# MACH.net
KiCad netlist of a schematic drawn in Altium Designer
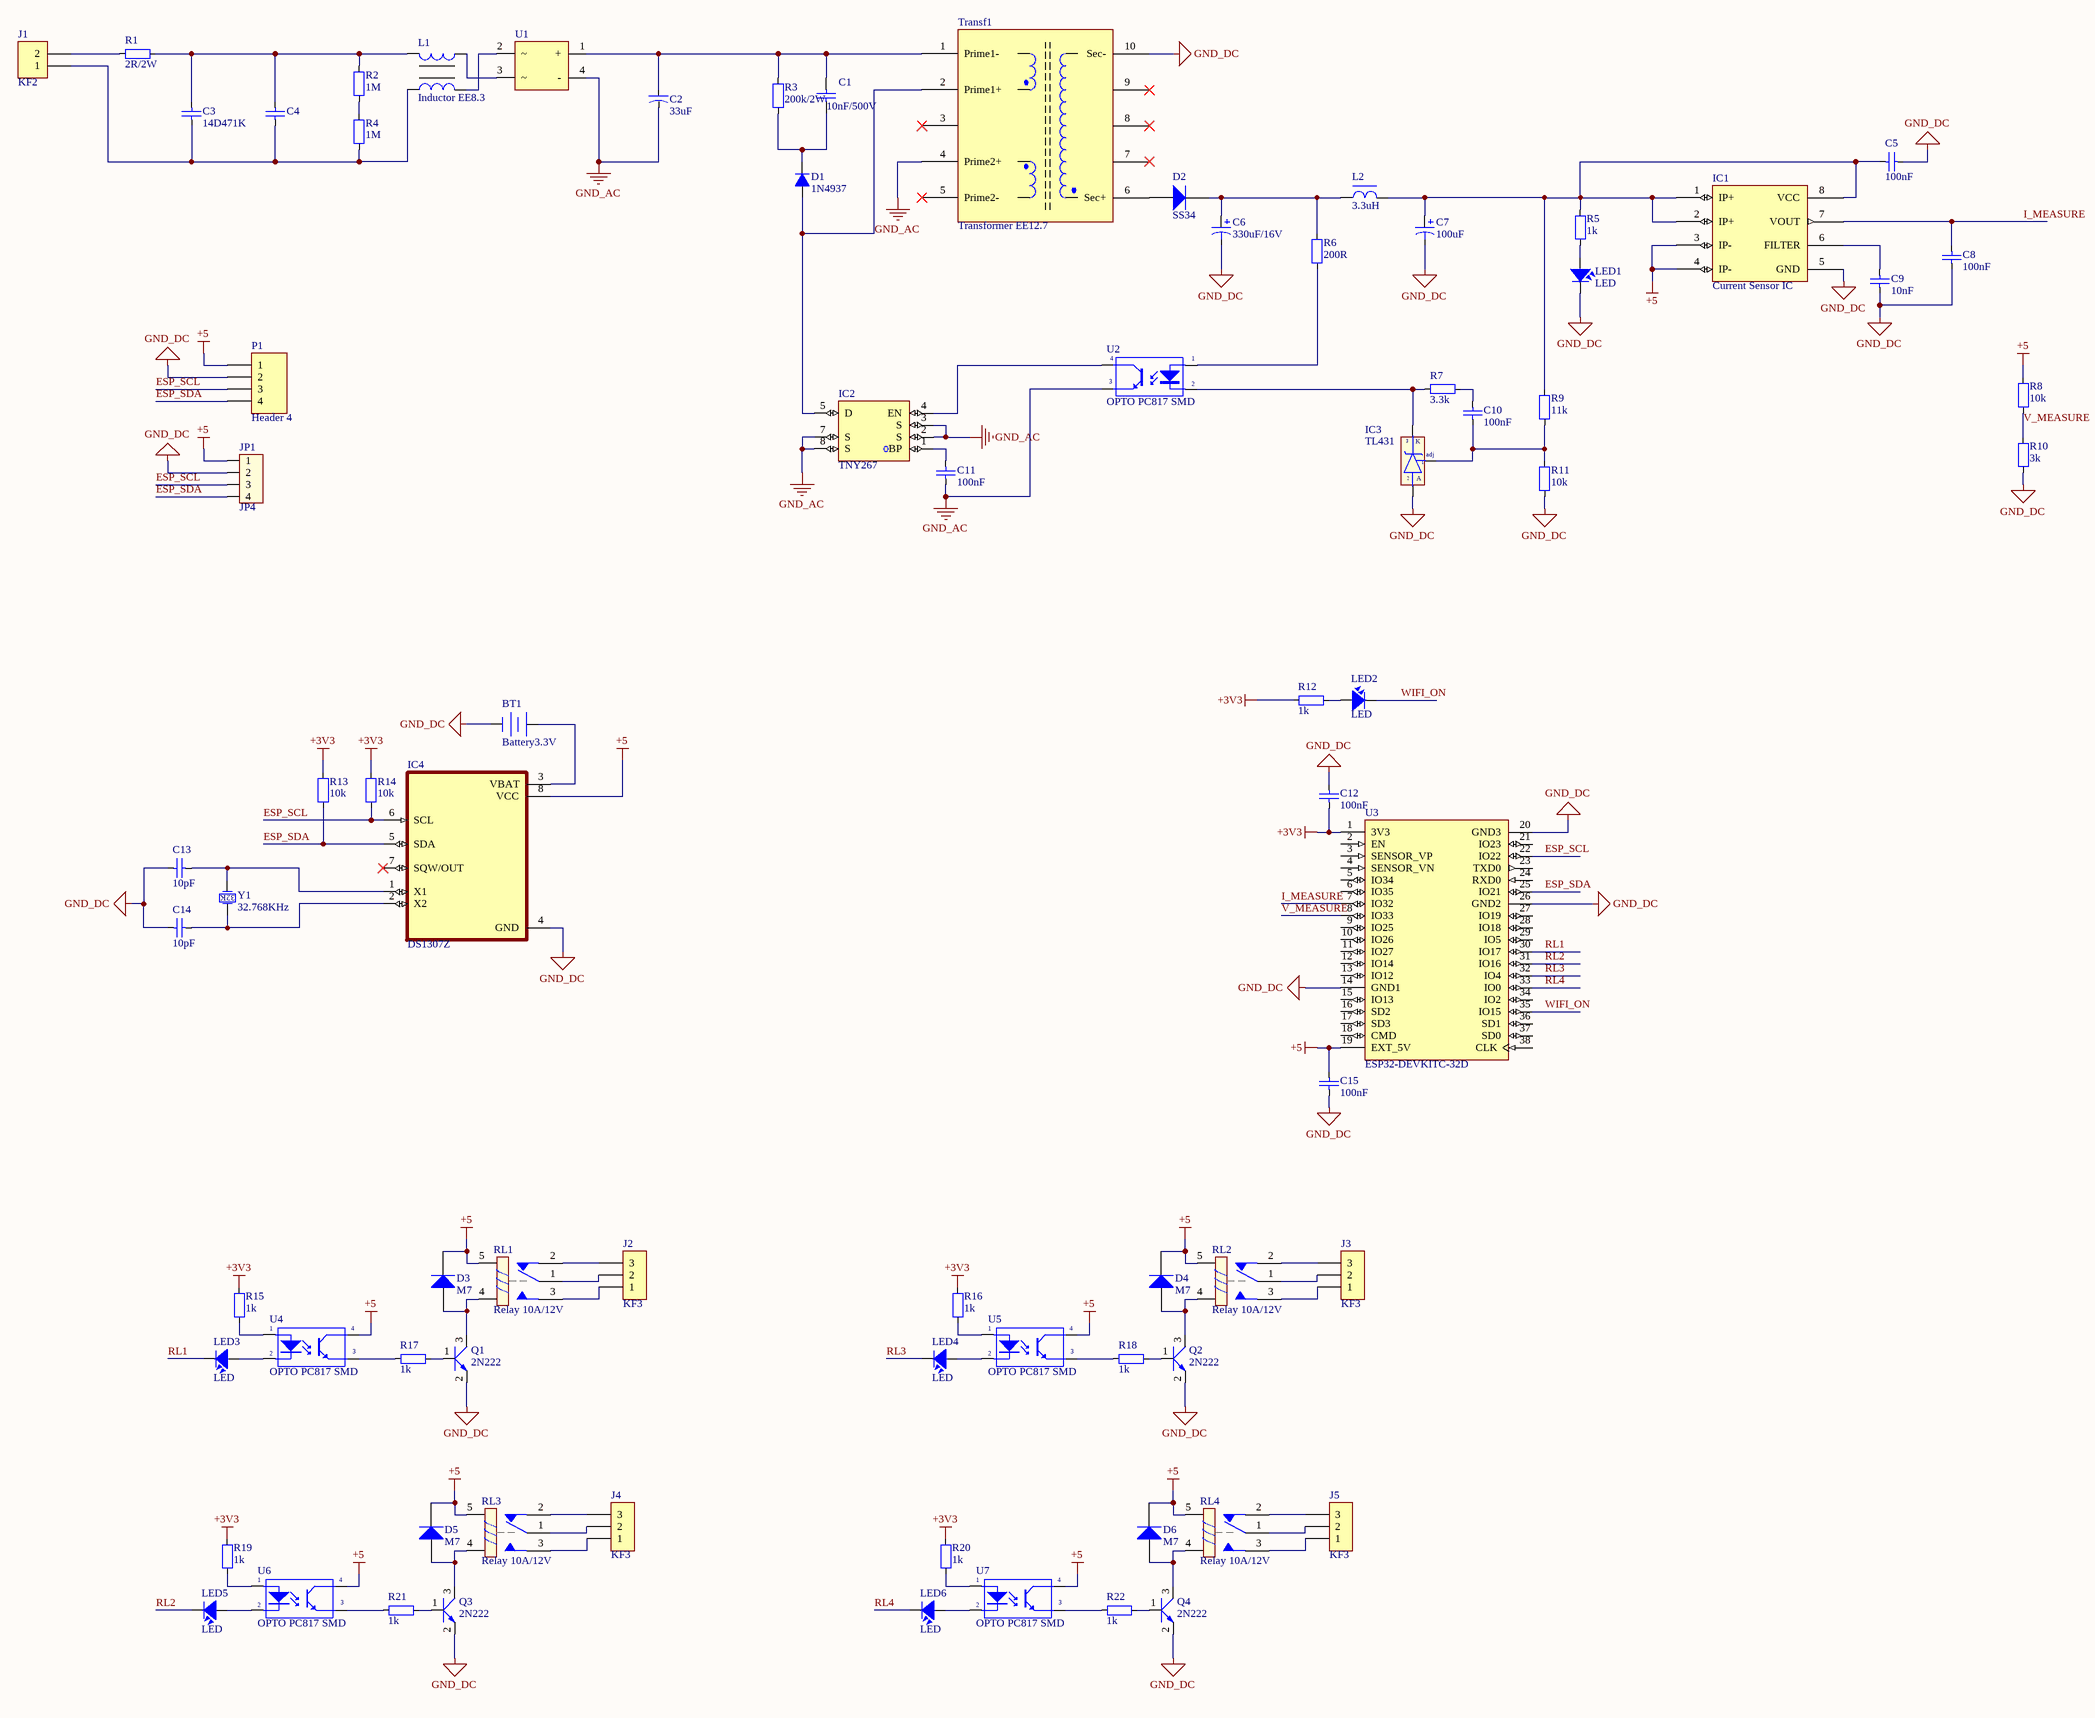
[diagram p0: MACH.SchDoc]

(export (version "E")
  (design (tool "Eeschema 10.0.6"))
  (components
    (comp (ref "BT1")
      (value "Battery3.3V")
      (footprint "CR1220 SMD")
      (description "Multicell Battery")
      (fields (field (name "PUBLISHER") "Altium Limited"))
      (libsource (lib "My Library") (part "Battery3.3V"))
    )
    (comp (ref "C1")
      (value "10nF/500V")
      (footprint "tu gom")
      (description "Tụ gốm 103 10nF 500V")
      (libsource (lib "Altium_Lib_by_KhueNguyenCreator") (part "Tu gom 103 50V"))
    )
    (comp (ref "C2")
      (value "33uF")
      (footprint "CA-ALU-8")
      (description "Capacitor (Semiconductor SIM Model)")
      (fields (field (name "PUBLISHER") "Altium Limited"))
      (libsource (lib "My Library") (part "CAP-ALU-DIP"))
    )
    (comp (ref "C3")
      (value "14D471K")
      (footprint "103/2KV")
      (description "Capacitor Ceramic 2KV")
      (fields (field (name "PUBLISHER") "Altium Limited"))
      (libsource (lib "My Library") (part "Cap2KV"))
    )
    (comp (ref "C4")
      (value "Cap AC filter")
      (footprint "Cap AC filter")
      (description "Tụ lọc nguồn AC 0.1uf 275v 10mm")
      (libsource (lib "My Library") (part "Cap AC filter"))
    )
    (comp (ref "C5")
      (value "100nF")
      (footprint "CAP_0805")
      (description "Capacitor")
      (fields (field (name "PUBLISHER") "Altium Limited"))
      (libsource (lib "My Library") (part "CapSMD"))
    )
    (comp (ref "C6")
      (value "330uF/16V")
      (footprint "C8mm")
      (description "Polarized Capacitor (Axial)")
      (fields (field (name "PUBLISHER") "Altium Limited"))
      (libsource (lib "My Library") (part "Cap Pol"))
    )
    (comp (ref "C7")
      (value "100uF")
      (footprint "C8mm")
      (description "Polarized Capacitor (Axial)")
      (fields (field (name "PUBLISHER") "Altium Limited"))
      (libsource (lib "My Library") (part "Cap Pol"))
    )
    (comp (ref "C8")
      (value "100nF")
      (footprint "CAP_0805")
      (description "Capacitor")
      (fields (field (name "PUBLISHER") "Altium Limited"))
      (libsource (lib "My Library") (part "CapSMD"))
    )
    (comp (ref "C9")
      (value "10nF")
      (footprint "CAP_0805")
      (description "Capacitor")
      (fields (field (name "PUBLISHER") "Altium Limited"))
      (libsource (lib "My Library") (part "CapSMD"))
    )
    (comp (ref "C10")
      (value "100nF")
      (footprint "CAP_0805")
      (description "Capacitor")
      (fields (field (name "PUBLISHER") "Altium Limited"))
      (libsource (lib "My Library") (part "CapSMD"))
    )
    (comp (ref "C11")
      (value "100nF")
      (footprint "CAP_0805")
      (description "Capacitor")
      (fields (field (name "PUBLISHER") "Altium Limited"))
      (libsource (lib "My Library") (part "CapSMD"))
    )
    (comp (ref "C12")
      (value "100nF")
      (footprint "CAP_0805")
      (description "Capacitor")
      (fields (field (name "PUBLISHER") "Altium Limited"))
      (libsource (lib "My Library") (part "CapSMD"))
    )
    (comp (ref "C13")
      (value "10pF")
      (footprint "CAP_0603")
      (description "Capacitor")
      (fields (field (name "PUBLISHER") "Altium Limited"))
      (libsource (lib "My Library") (part "CapSMD"))
    )
    (comp (ref "C14")
      (value "10pF")
      (footprint "CAP_0603")
      (description "Capacitor")
      (fields (field (name "PUBLISHER") "Altium Limited"))
      (libsource (lib "My Library") (part "CapSMD"))
    )
    (comp (ref "C15")
      (value "100nF")
      (footprint "CAP_0805")
      (description "Capacitor")
      (fields (field (name "PUBLISHER") "Altium Limited"))
      (libsource (lib "My Library") (part "CapSMD"))
    )
    (comp (ref "D1")
      (value "1N4937")
      (footprint "D5AN")
      (description "Diode 5A")
      (libsource (lib "My Library") (part "D5A"))
    )
    (comp (ref "D2")
      (value "SS34")
      (footprint "DIODE SMA")
      (description "Dán")
      (libsource (lib "Altium_Lib_by_KhueNguyenCreator") (part "Diode SS34 ( 1N5822 )"))
    )
    (comp (ref "D3")
      (value "M7")
      (footprint "DIODE SMA")
      (description "Dán")
      (libsource (lib "Altium_Lib_by_KhueNguyenCreator") (part "Diode M7 ( 4007 )"))
    )
    (comp (ref "D4")
      (value "M7")
      (footprint "DIODE SMA")
      (description "Dán")
      (libsource (lib "Altium_Lib_by_KhueNguyenCreator") (part "Diode M7 ( 4007 )"))
    )
    (comp (ref "D5")
      (value "M7")
      (footprint "DIODE SMA")
      (description "Dán")
      (libsource (lib "Altium_Lib_by_KhueNguyenCreator") (part "Diode M7 ( 4007 )"))
    )
    (comp (ref "D6")
      (value "M7")
      (footprint "DIODE SMA")
      (description "Dán")
      (libsource (lib "Altium_Lib_by_KhueNguyenCreator") (part "Diode M7 ( 4007 )"))
    )
    (comp (ref "IC1")
      (value "Current Sensor IC")
      (footprint "SOIC-8")
      (libsource (lib "My Library") (part "ACS712"))
    )
    (comp (ref "IC2")
      (value "TNY267")
      (footprint "TNY264")
      (description "IC Power")
      (libsource (lib "My Library") (part "TNY264"))
    )
    (comp (ref "IC3")
      (value "TL431")
      (footprint "qto-92")
      (description "Programmable Shunt Regulator")
      (libsource (lib "My Library") (part "TL431"))
    )
    (comp (ref "IC4")
      (value "DS1307Z")
      (footprint "SOIC-8")
      (description "0x68")
      (libsource (lib "My Library") (part "DS1307Z"))
    )
    (comp (ref "J1")
      (value "KF2")
      (footprint "KF2-5.08")
      (fields
        (field (name "MANUFACTURER") "Würth Elektronik eiSos GmbH")
        (field (name "PARTNO") "691103110002")
        (field (name "CREATED BY") "Karrer Zheng")
      )
      (libsource (lib "My Library") (part "KF2"))
    )
    (comp (ref "J2")
      (value "KF3")
      (footprint "KF3-5.08")
      (fields
        (field (name "MANUFACTURER") "Würth Elektronik eiSos GmbH")
        (field (name "PARTNO") "691103110003")
        (field (name "CREATED BY") "Karrer Zheng")
      )
      (libsource (lib "My Library") (part "KF3"))
    )
    (comp (ref "J3")
      (value "KF3")
      (footprint "KF3-5.08")
      (fields
        (field (name "MANUFACTURER") "Würth Elektronik eiSos GmbH")
        (field (name "PARTNO") "691103110003")
        (field (name "CREATED BY") "Karrer Zheng")
      )
      (libsource (lib "My Library") (part "KF3"))
    )
    (comp (ref "J4")
      (value "KF3")
      (footprint "KF3-5.08")
      (fields
        (field (name "MANUFACTURER") "Würth Elektronik eiSos GmbH")
        (field (name "PARTNO") "691103110003")
        (field (name "CREATED BY") "Karrer Zheng")
      )
      (libsource (lib "My Library") (part "KF3"))
    )
    (comp (ref "J5")
      (value "KF3")
      (footprint "KF3-5.08")
      (fields
        (field (name "MANUFACTURER") "Würth Elektronik eiSos GmbH")
        (field (name "PARTNO") "691103110003")
        (field (name "CREATED BY") "Karrer Zheng")
      )
      (libsource (lib "My Library") (part "KF3"))
    )
    (comp (ref "JP1")
      (value "JP4")
      (footprint "CON4")
      (description "Connector 4")
      (libsource (lib "My Library") (part "Con4"))
    )
    (comp (ref "L1")
      (value "Inductor EE8.3")
      (footprint "Inductor EE8.3")
      (libsource (lib "My Library") (part "Inductor EE8.3"))
    )
    (comp (ref "L2")
      (value "3.3uH")
      (footprint "L-SMD-M-7.3x4.5")
      (description "Inductor")
      (libsource (lib "My Library") (part "L-DIP-1"))
    )
    (comp (ref "LED1")
      (value "LED")
      (footprint "LED-0805-Red")
      (description "LED Single colour Green and Red")
      (libsource (lib "My Library") (part "LED"))
    )
    (comp (ref "LED2")
      (value "LED")
      (footprint "LED-0805-Red")
      (description "LED Single colour Green and Red")
      (libsource (lib "My Library") (part "LED"))
    )
    (comp (ref "LED3")
      (value "LED")
      (footprint "LED-0805-Red")
      (description "LED Single colour Green and Red")
      (libsource (lib "My Library") (part "LED"))
    )
    (comp (ref "LED4")
      (value "LED")
      (footprint "LED-0805-Red")
      (description "LED Single colour Green and Red")
      (libsource (lib "My Library") (part "LED"))
    )
    (comp (ref "LED5")
      (value "LED")
      (footprint "LED-0805-Red")
      (description "LED Single colour Green and Red")
      (libsource (lib "My Library") (part "LED"))
    )
    (comp (ref "LED6")
      (value "LED")
      (footprint "LED-0805-Red")
      (description "LED Single colour Green and Red")
      (libsource (lib "My Library") (part "LED"))
    )
    (comp (ref "P1")
      (value "Header 4")
      (footprint "HDR1X4")
      (description "Header, 4-Pin")
      (fields (field (name "PUBLISHER") "Altium Limited"))
      (libsource (lib "Miscellaneous Connectors") (part "Header 4"))
    )
    (comp (ref "Q1")
      (value "2N222")
      (footprint "SOT23D")
      (description "NPN 600mW, ECB")
      (libsource (lib "My Library") (part "2N222"))
    )
    (comp (ref "Q2")
      (value "2N222")
      (footprint "SOT23D")
      (description "NPN 600mW, ECB")
      (libsource (lib "My Library") (part "2N222"))
    )
    (comp (ref "Q3")
      (value "2N222")
      (footprint "SOT23D")
      (description "NPN 600mW, ECB")
      (libsource (lib "My Library") (part "2N222"))
    )
    (comp (ref "Q4")
      (value "2N222")
      (footprint "SOT23D")
      (description "NPN 600mW, ECB")
      (libsource (lib "My Library") (part "2N222"))
    )
    (comp (ref "R1")
      (value "2R/2W")
      (footprint "RES-1WD")
      (description "Resistor - DIP")
      (libsource (lib "My Library") (part "Resistor - DIP"))
    )
    (comp (ref "R2")
      (value "1M")
      (footprint "RES-SMD-1206")
      (description "Resistor")
      (fields
        (field (name "MANUFACTURER") "Generic Components")
        (field (name "PUBLISHER") "Altium Hobart Technology Centre")
      )
      (libsource (lib "My Library") (part "Resistor - SMD"))
    )
    (comp (ref "R3")
      (value "200k/2W")
      (footprint "RES-1WD")
      (description "Resistor - DIP")
      (libsource (lib "My Library") (part "Resistor - DIP"))
    )
    (comp (ref "R4")
      (value "1M")
      (footprint "RES-SMD-1206")
      (description "Resistor")
      (fields
        (field (name "MANUFACTURER") "Generic Components")
        (field (name "PUBLISHER") "Altium Hobart Technology Centre")
      )
      (libsource (lib "My Library") (part "Resistor - SMD"))
    )
    (comp (ref "R5")
      (value "1k")
      (footprint "RES-SMD-0805")
      (description "Resistor")
      (fields
        (field (name "MANUFACTURER") "Generic Components")
        (field (name "PUBLISHER") "Altium Hobart Technology Centre")
      )
      (libsource (lib "My Library") (part "Resistor - SMD"))
    )
    (comp (ref "R6")
      (value "200R")
      (footprint "RES-SMD-0805")
      (description "Resistor")
      (fields
        (field (name "MANUFACTURER") "Generic Components")
        (field (name "PUBLISHER") "Altium Hobart Technology Centre")
      )
      (libsource (lib "My Library") (part "Resistor - SMD"))
    )
    (comp (ref "R7")
      (value "3.3k")
      (footprint "RES-SMD-0805")
      (description "Resistor")
      (fields
        (field (name "MANUFACTURER") "Generic Components")
        (field (name "PUBLISHER") "Altium Hobart Technology Centre")
      )
      (libsource (lib "My Library") (part "Resistor - SMD"))
    )
    (comp (ref "R8")
      (value "10k")
      (footprint "RES-SMD-0805")
      (description "Resistor")
      (fields
        (field (name "MANUFACTURER") "Generic Components")
        (field (name "PUBLISHER") "Altium Hobart Technology Centre")
      )
      (libsource (lib "My Library") (part "Resistor - SMD"))
    )
    (comp (ref "R9")
      (value "11k")
      (footprint "RES-SMD-0805")
      (description "Resistor")
      (fields
        (field (name "MANUFACTURER") "Generic Components")
        (field (name "PUBLISHER") "Altium Hobart Technology Centre")
      )
      (libsource (lib "My Library") (part "Resistor - SMD"))
    )
    (comp (ref "R10")
      (value "3k")
      (footprint "RES-SMD-0805")
      (description "Resistor")
      (fields
        (field (name "MANUFACTURER") "Generic Components")
        (field (name "PUBLISHER") "Altium Hobart Technology Centre")
      )
      (libsource (lib "My Library") (part "Resistor - SMD"))
    )
    (comp (ref "R11")
      (value "10k")
      (footprint "RES-SMD-0805")
      (description "Resistor")
      (fields
        (field (name "MANUFACTURER") "Generic Components")
        (field (name "PUBLISHER") "Altium Hobart Technology Centre")
      )
      (libsource (lib "My Library") (part "Resistor - SMD"))
    )
    (comp (ref "R12")
      (value "1k")
      (footprint "RES-SMD-0805")
      (description "Resistor")
      (fields
        (field (name "MANUFACTURER") "Generic Components")
        (field (name "PUBLISHER") "Altium Hobart Technology Centre")
      )
      (libsource (lib "My Library") (part "Resistor - SMD"))
    )
    (comp (ref "R13")
      (value "10k")
      (footprint "RES-SMD-0805")
      (description "Resistor")
      (fields
        (field (name "MANUFACTURER") "Generic Components")
        (field (name "PUBLISHER") "Altium Hobart Technology Centre")
      )
      (libsource (lib "My Library") (part "Resistor - SMD"))
    )
    (comp (ref "R14")
      (value "10k")
      (footprint "RES-SMD-0805")
      (description "Resistor")
      (fields
        (field (name "MANUFACTURER") "Generic Components")
        (field (name "PUBLISHER") "Altium Hobart Technology Centre")
      )
      (libsource (lib "My Library") (part "Resistor - SMD"))
    )
    (comp (ref "R15")
      (value "1k")
      (footprint "RES-SMD-0805")
      (description "Resistor")
      (fields
        (field (name "MANUFACTURER") "Generic Components")
        (field (name "PUBLISHER") "Altium Hobart Technology Centre")
      )
      (libsource (lib "My Library") (part "Resistor - SMD"))
    )
    (comp (ref "R16")
      (value "1k")
      (footprint "RES-SMD-0805")
      (description "Resistor")
      (fields
        (field (name "MANUFACTURER") "Generic Components")
        (field (name "PUBLISHER") "Altium Hobart Technology Centre")
      )
      (libsource (lib "My Library") (part "Resistor - SMD"))
    )
    (comp (ref "R17")
      (value "1k")
      (footprint "RES-SMD-0805")
      (description "Resistor")
      (fields
        (field (name "MANUFACTURER") "Generic Components")
        (field (name "PUBLISHER") "Altium Hobart Technology Centre")
      )
      (libsource (lib "My Library") (part "Resistor - SMD"))
    )
    (comp (ref "R18")
      (value "1k")
      (footprint "RES-SMD-0805")
      (description "Resistor")
      (fields
        (field (name "MANUFACTURER") "Generic Components")
        (field (name "PUBLISHER") "Altium Hobart Technology Centre")
      )
      (libsource (lib "My Library") (part "Resistor - SMD"))
    )
    (comp (ref "R19")
      (value "1k")
      (footprint "RES-SMD-0805")
      (description "Resistor")
      (fields
        (field (name "MANUFACTURER") "Generic Components")
        (field (name "PUBLISHER") "Altium Hobart Technology Centre")
      )
      (libsource (lib "My Library") (part "Resistor - SMD"))
    )
    (comp (ref "R20")
      (value "1k")
      (footprint "RES-SMD-0805")
      (description "Resistor")
      (fields
        (field (name "MANUFACTURER") "Generic Components")
        (field (name "PUBLISHER") "Altium Hobart Technology Centre")
      )
      (libsource (lib "My Library") (part "Resistor - SMD"))
    )
    (comp (ref "R21")
      (value "1k")
      (footprint "RES-SMD-0805")
      (description "Resistor")
      (fields
        (field (name "MANUFACTURER") "Generic Components")
        (field (name "PUBLISHER") "Altium Hobart Technology Centre")
      )
      (libsource (lib "My Library") (part "Resistor - SMD"))
    )
    (comp (ref "R22")
      (value "1k")
      (footprint "RES-SMD-0805")
      (description "Resistor")
      (fields
        (field (name "MANUFACTURER") "Generic Components")
        (field (name "PUBLISHER") "Altium Hobart Technology Centre")
      )
      (libsource (lib "My Library") (part "Resistor - SMD"))
    )
    (comp (ref "RL1")
      (value "Relay 10A/12V")
      (footprint "RELAY 5")
      (description "Relay SPDT,10A - 12VDC 5 Pin")
      (libsource (lib "My Library") (part "Relay 5"))
    )
    (comp (ref "RL2")
      (value "Relay 10A/12V")
      (footprint "RELAY 5")
      (description "Relay SPDT,10A - 12VDC 5 Pin")
      (libsource (lib "My Library") (part "Relay 5"))
    )
    (comp (ref "RL3")
      (value "Relay 10A/12V")
      (footprint "RELAY 5")
      (description "Relay SPDT,10A - 12VDC 5 Pin")
      (libsource (lib "My Library") (part "Relay 5"))
    )
    (comp (ref "RL4")
      (value "Relay 10A/12V")
      (footprint "RELAY 5")
      (description "Relay SPDT,10A - 12VDC 5 Pin")
      (libsource (lib "My Library") (part "Relay 5"))
    )
    (comp (ref "Transf1")
      (value "Transformer EE12.7")
      (footprint "Transformer EE12.7")
      (libsource (lib "My Library") (part "Tranformer EE16"))
    )
    (comp (ref "U1")
      (value "Diode Bridge Flate")
      (footprint "DB207S")
      (description "Diode Bridge")
      (libsource (lib "My Library") (part "Diode Bridge Flate"))
    )
    (comp (ref "U2")
      (value "OPTO PC817 SMD")
      (footprint "SOP4")
      (description "Single Opto")
      (libsource (lib "Altium_Lib_by_KhueNguyenCreator") (part "OPTO PC817 SMD"))
    )
    (comp (ref "U3")
      (value "ESP32-DEVKITC-32D")
      (footprint "MODULE_ESP32-DEVKITC-32D")
      (description "EVAL BOARD FOR ESP-WROOM-32")
      (fields (field (name "MF") "Espressif Systems"))
      (libsource (lib "My Library") (part "ESP32-DEVKITC-32D"))
    )
    (comp (ref "U4")
      (value "OPTO PC817 SMD")
      (footprint "SOP4")
      (description "Single Opto")
      (libsource (lib "Altium_Lib_by_KhueNguyenCreator") (part "OPTO PC817 SMD"))
    )
    (comp (ref "U5")
      (value "OPTO PC817 SMD")
      (footprint "SOP4")
      (description "Single Opto")
      (libsource (lib "Altium_Lib_by_KhueNguyenCreator") (part "OPTO PC817 SMD"))
    )
    (comp (ref "U6")
      (value "OPTO PC817 SMD")
      (footprint "SOP4")
      (description "Single Opto")
      (libsource (lib "Altium_Lib_by_KhueNguyenCreator") (part "OPTO PC817 SMD"))
    )
    (comp (ref "U7")
      (value "OPTO PC817 SMD")
      (footprint "SOP4")
      (description "Single Opto")
      (libsource (lib "Altium_Lib_by_KhueNguyenCreator") (part "OPTO PC817 SMD"))
    )
    (comp (ref "Y1")
      (value "32.768KHz")
      (footprint "XTAL32K")
      (description "Crystal Oscillator")
      (fields (field (name "PUBLISHER") "Altium Limited"))
      (libsource (lib "My Library") (part "XTAL/32KHz"))
    )
  )
  (nets
    (net (code "1") (name "+3V3") (class "Default")
      (node (ref "C12") (pin "1") (pinfunction "1_1") (pintype "passive"))
      (node (ref "R12") (pin "2") (pinfunction "2_2") (pintype "passive"))
      (node (ref "R13") (pin "1") (pinfunction "1_1") (pintype "passive"))
      (node (ref "R14") (pin "1") (pinfunction "1_1") (pintype "passive"))
      (node (ref "R15") (pin "1") (pinfunction "1_1") (pintype "passive"))
      (node (ref "R16") (pin "1") (pinfunction "1_1") (pintype "passive"))
      (node (ref "R19") (pin "1") (pinfunction "1_1") (pintype "passive"))
      (node (ref "R20") (pin "1") (pinfunction "1_1") (pintype "passive"))
      (node (ref "U3") (pin "1") (pinfunction "3V3_1") (pintype "power_in"))
    )
    (net (code "2") (name "+5") (class "Default")
      (node (ref "C15") (pin "2") (pinfunction "2_2") (pintype "passive"))
      (node (ref "D3") (pin "2") (pinfunction "K_2") (pintype "passive"))
      (node (ref "D4") (pin "2") (pinfunction "K_2") (pintype "passive"))
      (node (ref "D5") (pin "2") (pinfunction "K_2") (pintype "passive"))
      (node (ref "D6") (pin "2") (pinfunction "K_2") (pintype "passive"))
      (node (ref "IC1") (pin "3") (pinfunction "IP-_3") (pintype "bidirectional"))
      (node (ref "IC1") (pin "4") (pinfunction "IP-_4") (pintype "bidirectional"))
      (node (ref "IC4") (pin "8") (pinfunction "VCC_8") (pintype "power_in"))
      (node (ref "JP1") (pin "1") (pinfunction "1_1") (pintype "passive"))
      (node (ref "P1") (pin "1") (pinfunction "1_1") (pintype "passive"))
      (node (ref "R8") (pin "1") (pinfunction "1_1") (pintype "passive"))
      (node (ref "RL1") (pin "5") (pinfunction "5_5") (pintype "passive"))
      (node (ref "RL2") (pin "5") (pinfunction "5_5") (pintype "passive"))
      (node (ref "RL3") (pin "5") (pinfunction "5_5") (pintype "passive"))
      (node (ref "RL4") (pin "5") (pinfunction "5_5") (pintype "passive"))
      (node (ref "U3") (pin "19") (pinfunction "EXT_5V_19") (pintype "power_in"))
      (node (ref "U4") (pin "4") (pinfunction "C_4") (pintype "passive"))
      (node (ref "U5") (pin "4") (pinfunction "C_4") (pintype "passive"))
      (node (ref "U6") (pin "4") (pinfunction "C_4") (pintype "passive"))
      (node (ref "U7") (pin "4") (pinfunction "C_4") (pintype "passive"))
    )
    (net (code "3") (name "/ESP_SCL") (class "Default")
      (node (ref "IC4") (pin "6") (pinfunction "SCL_6") (pintype "input"))
      (node (ref "JP1") (pin "3") (pinfunction "3_3") (pintype "passive"))
      (node (ref "P1") (pin "3") (pinfunction "3_3") (pintype "passive"))
      (node (ref "R14") (pin "2") (pinfunction "2_2") (pintype "passive"))
      (node (ref "U3") (pin "22") (pinfunction "IO22_22") (pintype "bidirectional"))
    )
    (net (code "4") (name "/ESP_SDA") (class "Default")
      (node (ref "IC4") (pin "5") (pinfunction "SDA_5") (pintype "bidirectional"))
      (node (ref "JP1") (pin "4") (pinfunction "4_4") (pintype "passive"))
      (node (ref "P1") (pin "4") (pinfunction "4_4") (pintype "passive"))
      (node (ref "R13") (pin "2") (pinfunction "2_2") (pintype "passive"))
      (node (ref "U3") (pin "25") (pinfunction "IO21_25") (pintype "bidirectional"))
    )
    (net (code "5") (name "/I_MEASURE") (class "Default")
      (node (ref "C8") (pin "2") (pinfunction "2_2") (pintype "passive"))
      (node (ref "IC1") (pin "7") (pinfunction "VOUT_7") (pintype "output"))
      (node (ref "U3") (pin "7") (pinfunction "IO32_7") (pintype "bidirectional"))
    )
    (net (code "6") (name "/RL1") (class "Default")
      (node (ref "LED3") (pin "2") (pinfunction "2_2") (pintype "passive"))
      (node (ref "U3") (pin "30") (pinfunction "IO17_30") (pintype "bidirectional"))
    )
    (net (code "7") (name "/RL2") (class "Default")
      (node (ref "LED5") (pin "2") (pinfunction "2_2") (pintype "passive"))
      (node (ref "U3") (pin "31") (pinfunction "IO16_31") (pintype "bidirectional"))
    )
    (net (code "8") (name "/RL3") (class "Default")
      (node (ref "LED4") (pin "2") (pinfunction "2_2") (pintype "passive"))
      (node (ref "U3") (pin "32") (pinfunction "IO4_32") (pintype "bidirectional"))
    )
    (net (code "9") (name "/RL4") (class "Default")
      (node (ref "LED6") (pin "2") (pinfunction "2_2") (pintype "passive"))
      (node (ref "U3") (pin "33") (pinfunction "IO0_33") (pintype "bidirectional"))
    )
    (net (code "10") (name "/V_MEASURE") (class "Default")
      (node (ref "R10") (pin "2") (pinfunction "2_2") (pintype "passive"))
      (node (ref "R8") (pin "2") (pinfunction "2_2") (pintype "passive"))
      (node (ref "U3") (pin "8") (pinfunction "IO33_8") (pintype "bidirectional"))
    )
    (net (code "11") (name "/WIFI_ON") (class "Default")
      (node (ref "LED2") (pin "2") (pinfunction "2_2") (pintype "passive"))
      (node (ref "U3") (pin "35") (pinfunction "IO15_35") (pintype "bidirectional"))
    )
    (net (code "12") (name "GND") (class "Default")
      (node (ref "Y1") (pin "0") (pinfunction "0_0") (pintype "passive"))
    )
    (net (code "13") (name "GND_AC") (class "Default")
      (node (ref "C11") (pin "1") (pinfunction "1_1") (pintype "passive"))
      (node (ref "C2") (pin "2") (pinfunction "2_2") (pintype "passive"))
      (node (ref "IC2") (pin "2") (pinfunction "S_2") (pintype "bidirectional"))
      (node (ref "IC2") (pin "3") (pinfunction "S_3") (pintype "bidirectional"))
      (node (ref "IC2") (pin "7") (pinfunction "S_7") (pintype "bidirectional"))
      (node (ref "IC2") (pin "8") (pinfunction "S_8") (pintype "bidirectional"))
      (node (ref "Transf1") (pin "4") (pinfunction "Prime2+_4") (pintype "passive"))
      (node (ref "U1") (pin "4") (pinfunction "-_4") (pintype "passive"))
      (node (ref "U2") (pin "3") (pinfunction "E_3") (pintype "passive"))
    )
    (net (code "14") (name "GND_DC") (class "Default")
      (node (ref "BT1") (pin "2") (pinfunction "-_2") (pintype "passive"))
      (node (ref "C12") (pin "2") (pinfunction "2_2") (pintype "passive"))
      (node (ref "C13") (pin "1") (pinfunction "1_1") (pintype "passive"))
      (node (ref "C14") (pin "1") (pinfunction "1_1") (pintype "passive"))
      (node (ref "C15") (pin "1") (pinfunction "1_1") (pintype "passive"))
      (node (ref "C5") (pin "2") (pinfunction "2_2") (pintype "passive"))
      (node (ref "C6") (pin "2") (pinfunction "2_2") (pintype "passive"))
      (node (ref "C7") (pin "2") (pinfunction "2_2") (pintype "passive"))
      (node (ref "C8") (pin "1") (pinfunction "1_1") (pintype "passive"))
      (node (ref "C9") (pin "2") (pinfunction "2_2") (pintype "passive"))
      (node (ref "IC1") (pin "5") (pinfunction "GND_5") (pintype "passive"))
      (node (ref "IC3") (pin "2") (pinfunction "A_2") (pintype "passive"))
      (node (ref "IC4") (pin "4") (pinfunction "GND_4") (pintype "power_in"))
      (node (ref "JP1") (pin "2") (pinfunction "2_2") (pintype "passive"))
      (node (ref "LED1") (pin "2") (pinfunction "2_2") (pintype "passive"))
      (node (ref "P1") (pin "2") (pinfunction "2_2") (pintype "passive"))
      (node (ref "Q1") (pin "2") (pinfunction "E_2") (pintype "passive"))
      (node (ref "Q2") (pin "2") (pinfunction "E_2") (pintype "passive"))
      (node (ref "Q3") (pin "2") (pinfunction "E_2") (pintype "passive"))
      (node (ref "Q4") (pin "2") (pinfunction "E_2") (pintype "passive"))
      (node (ref "R10") (pin "1") (pinfunction "1_1") (pintype "passive"))
      (node (ref "R11") (pin "1") (pinfunction "1_1") (pintype "passive"))
      (node (ref "Transf1") (pin "10") (pinfunction "Sec-_10") (pintype "passive"))
      (node (ref "U3") (pin "14") (pinfunction "GND1_14") (pintype "power_in"))
      (node (ref "U3") (pin "20") (pinfunction "GND3_20") (pintype "power_in"))
      (node (ref "U3") (pin "26") (pinfunction "GND2_26") (pintype "power_in"))
    )
    (net (code "15") (name "Net-(BT1-+)") (class "Default")
      (node (ref "BT1") (pin "1") (pinfunction "+_1") (pintype "passive"))
      (node (ref "IC4") (pin "3") (pinfunction "VBAT_3") (pintype "power_in"))
    )
    (net (code "16") (name "Net-(C3-Pad1)") (class "Default")
      (node (ref "C3") (pin "1") (pinfunction "1_1") (pintype "passive"))
      (node (ref "C4") (pin "1") (pinfunction "1_1") (pintype "passive"))
      (node (ref "J1") (pin "1") (pinfunction "1_1") (pintype "passive"))
      (node (ref "L1") (pin "3") (pinfunction "3_3") (pintype "passive"))
      (node (ref "R4") (pin "1") (pinfunction "1_1") (pintype "passive"))
    )
    (net (code "17") (name "Net-(C3-Pad2)") (class "Default")
      (node (ref "C3") (pin "2") (pinfunction "2_2") (pintype "passive"))
      (node (ref "C4") (pin "2") (pinfunction "2_2") (pintype "passive"))
      (node (ref "L1") (pin "1") (pinfunction "1_1") (pintype "passive"))
      (node (ref "R1") (pin "1") (pinfunction "1_1") (pintype "passive"))
      (node (ref "R2") (pin "2") (pinfunction "2_2") (pintype "passive"))
    )
    (net (code "18") (name "Net-(C10-Pad2)") (class "Default")
      (node (ref "C10") (pin "2") (pinfunction "2_2") (pintype "passive"))
      (node (ref "R7") (pin "1") (pinfunction "1_1") (pintype "passive"))
    )
    (net (code "19") (name "Net-(D1-A)") (class "Default")
      (node (ref "D1") (pin "1") (pinfunction "A_1") (pintype "passive"))
      (node (ref "IC2") (pin "5") (pinfunction "D_5") (pintype "bidirectional"))
      (node (ref "Transf1") (pin "2") (pinfunction "Prime1+_2") (pintype "passive"))
    )
    (net (code "20") (name "Net-(D1-K)") (class "Default")
      (node (ref "C1") (pin "2") (pinfunction "2_2") (pintype "passive"))
      (node (ref "D1") (pin "2") (pinfunction "K_2") (pintype "passive"))
      (node (ref "R3") (pin "1") (pinfunction "1_1") (pintype "passive"))
    )
    (net (code "21") (name "Net-(D2-A)") (class "Default")
      (node (ref "D2") (pin "1") (pinfunction "A_1") (pintype "passive"))
      (node (ref "Transf1") (pin "6") (pinfunction "Sec+_6") (pintype "passive"))
    )
    (net (code "22") (name "Net-(D2-K)") (class "Default")
      (node (ref "C6") (pin "1") (pinfunction "1_1") (pintype "passive"))
      (node (ref "D2") (pin "2") (pinfunction "K_2") (pintype "passive"))
      (node (ref "L2") (pin "1") (pinfunction "1_1") (pintype "passive"))
      (node (ref "R6") (pin "2") (pinfunction "2_2") (pintype "passive"))
    )
    (net (code "23") (name "Net-(D3-A)") (class "Default")
      (node (ref "D3") (pin "1") (pinfunction "A_1") (pintype "passive"))
      (node (ref "Q1") (pin "3") (pinfunction "C_3") (pintype "passive"))
      (node (ref "RL1") (pin "4") (pinfunction "4_4") (pintype "passive"))
    )
    (net (code "24") (name "Net-(D4-A)") (class "Default")
      (node (ref "D4") (pin "1") (pinfunction "A_1") (pintype "passive"))
      (node (ref "Q2") (pin "3") (pinfunction "C_3") (pintype "passive"))
      (node (ref "RL2") (pin "4") (pinfunction "4_4") (pintype "passive"))
    )
    (net (code "25") (name "Net-(D5-A)") (class "Default")
      (node (ref "D5") (pin "1") (pinfunction "A_1") (pintype "passive"))
      (node (ref "Q3") (pin "3") (pinfunction "C_3") (pintype "passive"))
      (node (ref "RL3") (pin "4") (pinfunction "4_4") (pintype "passive"))
    )
    (net (code "26") (name "Net-(D6-A)") (class "Default")
      (node (ref "D6") (pin "1") (pinfunction "A_1") (pintype "passive"))
      (node (ref "Q4") (pin "3") (pinfunction "C_3") (pintype "passive"))
      (node (ref "RL4") (pin "4") (pinfunction "4_4") (pintype "passive"))
    )
    (net (code "27") (name "Net-(IC1-FILTER)") (class "Default")
      (node (ref "C9") (pin "1") (pinfunction "1_1") (pintype "passive"))
      (node (ref "IC1") (pin "6") (pinfunction "FILTER_6") (pintype "passive"))
    )
    (net (code "28") (name "Net-(IC1-VCC)") (class "Default")
      (node (ref "C5") (pin "1") (pinfunction "1_1") (pintype "passive"))
      (node (ref "C7") (pin "1") (pinfunction "1_1") (pintype "passive"))
      (node (ref "IC1") (pin "1") (pinfunction "IP+_1") (pintype "bidirectional"))
      (node (ref "IC1") (pin "2") (pinfunction "IP+_2") (pintype "bidirectional"))
      (node (ref "IC1") (pin "8") (pinfunction "VCC_8") (pintype "passive"))
      (node (ref "L2") (pin "2") (pinfunction "2_2") (pintype "passive"))
      (node (ref "R5") (pin "2") (pinfunction "2_2") (pintype "passive"))
      (node (ref "R9") (pin "2") (pinfunction "2_2") (pintype "passive"))
    )
    (net (code "29") (name "Net-(IC2-BP)") (class "Default")
      (node (ref "C11") (pin "2") (pinfunction "2_2") (pintype "passive"))
      (node (ref "IC2") (pin "1") (pinfunction "BP_1") (pintype "bidirectional"))
    )
    (net (code "30") (name "Net-(IC2-EN)") (class "Default")
      (node (ref "IC2") (pin "4") (pinfunction "EN_4") (pintype "bidirectional"))
      (node (ref "U2") (pin "4") (pinfunction "C_4") (pintype "passive"))
    )
    (net (code "31") (name "Net-(IC3-K)") (class "Default")
      (node (ref "IC3") (pin "3") (pinfunction "K_3") (pintype "passive"))
      (node (ref "R7") (pin "2") (pinfunction "2_2") (pintype "passive"))
      (node (ref "U2") (pin "2") (pinfunction "K_2") (pintype "passive"))
    )
    (net (code "32") (name "Net-(IC3-adj)") (class "Default")
      (node (ref "C10") (pin "1") (pinfunction "1_1") (pintype "passive"))
      (node (ref "IC3") (pin "1") (pinfunction "adj_1") (pintype "passive"))
      (node (ref "R11") (pin "2") (pinfunction "2_2") (pintype "passive"))
      (node (ref "R9") (pin "1") (pinfunction "1_1") (pintype "passive"))
    )
    (net (code "33") (name "Net-(IC4-X1)") (class "Default")
      (node (ref "C13") (pin "2") (pinfunction "2_2") (pintype "passive"))
      (node (ref "IC4") (pin "1") (pinfunction "X1_1") (pintype "bidirectional"))
      (node (ref "Y1") (pin "2") (pinfunction "OSC2_2") (pintype "passive"))
    )
    (net (code "34") (name "Net-(IC4-X2)") (class "Default")
      (node (ref "C14") (pin "2") (pinfunction "2_2") (pintype "passive"))
      (node (ref "IC4") (pin "2") (pinfunction "X2_2") (pintype "bidirectional"))
      (node (ref "Y1") (pin "1") (pinfunction "OSC1_1") (pintype "passive"))
    )
    (net (code "35") (name "Net-(J1-Pad2)") (class "Default")
      (node (ref "J1") (pin "2") (pinfunction "2_2") (pintype "passive"))
      (node (ref "R1") (pin "2") (pinfunction "2_2") (pintype "passive"))
    )
    (net (code "36") (name "Net-(J2-Pad1)") (class "Default")
      (node (ref "J2") (pin "1") (pinfunction "1_1") (pintype "passive"))
      (node (ref "RL1") (pin "3") (pinfunction "3_3") (pintype "passive"))
    )
    (net (code "37") (name "Net-(J2-Pad2)") (class "Default")
      (node (ref "J2") (pin "2") (pinfunction "2_2") (pintype "passive"))
      (node (ref "RL1") (pin "1") (pinfunction "1_1") (pintype "passive"))
    )
    (net (code "38") (name "Net-(J2-Pad3)") (class "Default")
      (node (ref "J2") (pin "3") (pinfunction "3_3") (pintype "passive"))
      (node (ref "RL1") (pin "2") (pinfunction "2_2") (pintype "passive"))
    )
    (net (code "39") (name "Net-(J3-Pad1)") (class "Default")
      (node (ref "J3") (pin "1") (pinfunction "1_1") (pintype "passive"))
      (node (ref "RL2") (pin "3") (pinfunction "3_3") (pintype "passive"))
    )
    (net (code "40") (name "Net-(J3-Pad2)") (class "Default")
      (node (ref "J3") (pin "2") (pinfunction "2_2") (pintype "passive"))
      (node (ref "RL2") (pin "1") (pinfunction "1_1") (pintype "passive"))
    )
    (net (code "41") (name "Net-(J3-Pad3)") (class "Default")
      (node (ref "J3") (pin "3") (pinfunction "3_3") (pintype "passive"))
      (node (ref "RL2") (pin "2") (pinfunction "2_2") (pintype "passive"))
    )
    (net (code "42") (name "Net-(J4-Pad1)") (class "Default")
      (node (ref "J4") (pin "1") (pinfunction "1_1") (pintype "passive"))
      (node (ref "RL3") (pin "3") (pinfunction "3_3") (pintype "passive"))
    )
    (net (code "43") (name "Net-(J4-Pad2)") (class "Default")
      (node (ref "J4") (pin "2") (pinfunction "2_2") (pintype "passive"))
      (node (ref "RL3") (pin "1") (pinfunction "1_1") (pintype "passive"))
    )
    (net (code "44") (name "Net-(J4-Pad3)") (class "Default")
      (node (ref "J4") (pin "3") (pinfunction "3_3") (pintype "passive"))
      (node (ref "RL3") (pin "2") (pinfunction "2_2") (pintype "passive"))
    )
    (net (code "45") (name "Net-(J5-Pad1)") (class "Default")
      (node (ref "J5") (pin "1") (pinfunction "1_1") (pintype "passive"))
      (node (ref "RL4") (pin "3") (pinfunction "3_3") (pintype "passive"))
    )
    (net (code "46") (name "Net-(J5-Pad2)") (class "Default")
      (node (ref "J5") (pin "2") (pinfunction "2_2") (pintype "passive"))
      (node (ref "RL4") (pin "1") (pinfunction "1_1") (pintype "passive"))
    )
    (net (code "47") (name "Net-(J5-Pad3)") (class "Default")
      (node (ref "J5") (pin "3") (pinfunction "3_3") (pintype "passive"))
      (node (ref "RL4") (pin "2") (pinfunction "2_2") (pintype "passive"))
    )
    (net (code "48") (name "Net-(L1-Pad2)") (class "Default")
      (node (ref "L1") (pin "2") (pinfunction "2_2") (pintype "passive"))
      (node (ref "U1") (pin "3") (pinfunction "~_3") (pintype "passive"))
    )
    (net (code "49") (name "Net-(L1-Pad4)") (class "Default")
      (node (ref "L1") (pin "4") (pinfunction "4_4") (pintype "passive"))
      (node (ref "U1") (pin "2") (pinfunction "~_2") (pintype "passive"))
    )
    (net (code "50") (name "Net-(LED1-Pad1)") (class "Default")
      (node (ref "LED1") (pin "1") (pinfunction "1_1") (pintype "passive"))
      (node (ref "R5") (pin "1") (pinfunction "1_1") (pintype "passive"))
    )
    (net (code "51") (name "Net-(LED2-Pad1)") (class "Default")
      (node (ref "LED2") (pin "1") (pinfunction "1_1") (pintype "passive"))
      (node (ref "R12") (pin "1") (pinfunction "1_1") (pintype "passive"))
    )
    (net (code "52") (name "Net-(Q1-B)") (class "Default")
      (node (ref "Q1") (pin "1") (pinfunction "B_1") (pintype "passive"))
      (node (ref "R17") (pin "2") (pinfunction "2_2") (pintype "passive"))
    )
    (net (code "53") (name "Net-(Q2-B)") (class "Default")
      (node (ref "Q2") (pin "1") (pinfunction "B_1") (pintype "passive"))
      (node (ref "R18") (pin "2") (pinfunction "2_2") (pintype "passive"))
    )
    (net (code "54") (name "Net-(Q3-B)") (class "Default")
      (node (ref "Q3") (pin "1") (pinfunction "B_1") (pintype "passive"))
      (node (ref "R21") (pin "2") (pinfunction "2_2") (pintype "passive"))
    )
    (net (code "55") (name "Net-(Q4-B)") (class "Default")
      (node (ref "Q4") (pin "1") (pinfunction "B_1") (pintype "passive"))
      (node (ref "R22") (pin "2") (pinfunction "2_2") (pintype "passive"))
    )
    (net (code "56") (name "Net-(R2-Pad1)") (class "Default")
      (node (ref "R2") (pin "1") (pinfunction "1_1") (pintype "passive"))
      (node (ref "R4") (pin "2") (pinfunction "2_2") (pintype "passive"))
    )
    (net (code "57") (name "Net-(Transf1-Prime1-)") (class "Default")
      (node (ref "C1") (pin "1") (pinfunction "1_1") (pintype "passive"))
      (node (ref "C2") (pin "1") (pinfunction "1_1") (pintype "passive"))
      (node (ref "R3") (pin "2") (pinfunction "2_2") (pintype "passive"))
      (node (ref "Transf1") (pin "1") (pinfunction "Prime1-_1") (pintype "passive"))
      (node (ref "U1") (pin "1") (pinfunction "+_1") (pintype "passive"))
    )
    (net (code "58") (name "Net-(U2-A)") (class "Default")
      (node (ref "R6") (pin "1") (pinfunction "1_1") (pintype "passive"))
      (node (ref "U2") (pin "1") (pinfunction "A_1") (pintype "passive"))
    )
    (net (code "59") (name "Net-(U4-A)") (class "Default")
      (node (ref "R15") (pin "2") (pinfunction "2_2") (pintype "passive"))
      (node (ref "U4") (pin "1") (pinfunction "A_1") (pintype "passive"))
    )
    (net (code "60") (name "Net-(U4-E)") (class "Default")
      (node (ref "R17") (pin "1") (pinfunction "1_1") (pintype "passive"))
      (node (ref "U4") (pin "3") (pinfunction "E_3") (pintype "passive"))
    )
    (net (code "61") (name "Net-(U4-K)") (class "Default")
      (node (ref "LED3") (pin "1") (pinfunction "1_1") (pintype "passive"))
      (node (ref "U4") (pin "2") (pinfunction "K_2") (pintype "passive"))
    )
    (net (code "62") (name "Net-(U5-A)") (class "Default")
      (node (ref "R16") (pin "2") (pinfunction "2_2") (pintype "passive"))
      (node (ref "U5") (pin "1") (pinfunction "A_1") (pintype "passive"))
    )
    (net (code "63") (name "Net-(U5-E)") (class "Default")
      (node (ref "R18") (pin "1") (pinfunction "1_1") (pintype "passive"))
      (node (ref "U5") (pin "3") (pinfunction "E_3") (pintype "passive"))
    )
    (net (code "64") (name "Net-(U5-K)") (class "Default")
      (node (ref "LED4") (pin "1") (pinfunction "1_1") (pintype "passive"))
      (node (ref "U5") (pin "2") (pinfunction "K_2") (pintype "passive"))
    )
    (net (code "65") (name "Net-(U6-A)") (class "Default")
      (node (ref "R19") (pin "2") (pinfunction "2_2") (pintype "passive"))
      (node (ref "U6") (pin "1") (pinfunction "A_1") (pintype "passive"))
    )
    (net (code "66") (name "Net-(U6-E)") (class "Default")
      (node (ref "R21") (pin "1") (pinfunction "1_1") (pintype "passive"))
      (node (ref "U6") (pin "3") (pinfunction "E_3") (pintype "passive"))
    )
    (net (code "67") (name "Net-(U6-K)") (class "Default")
      (node (ref "LED5") (pin "1") (pinfunction "1_1") (pintype "passive"))
      (node (ref "U6") (pin "2") (pinfunction "K_2") (pintype "passive"))
    )
    (net (code "68") (name "Net-(U7-A)") (class "Default")
      (node (ref "R20") (pin "2") (pinfunction "2_2") (pintype "passive"))
      (node (ref "U7") (pin "1") (pinfunction "A_1") (pintype "passive"))
    )
    (net (code "69") (name "Net-(U7-E)") (class "Default")
      (node (ref "R22") (pin "1") (pinfunction "1_1") (pintype "passive"))
      (node (ref "U7") (pin "3") (pinfunction "E_3") (pintype "passive"))
    )
    (net (code "70") (name "Net-(U7-K)") (class "Default")
      (node (ref "LED6") (pin "1") (pinfunction "1_1") (pintype "passive"))
      (node (ref "U7") (pin "2") (pinfunction "K_2") (pintype "passive"))
    )
    (net (code "71") (name "unconnected-(IC4-SQW{slash}OUT-Pad7)") (class "Default")
      (node (ref "IC4") (pin "7") (pinfunction "SQW/OUT_7") (pintype "bidirectional+no_connect"))
    )
    (net (code "72") (name "unconnected-(Transf1-Pad3)") (class "Default")
      (node (ref "Transf1") (pin "3") (pintype "passive+no_connect"))
    )
    (net (code "73") (name "unconnected-(Transf1-Pad7)") (class "Default")
      (node (ref "Transf1") (pin "7") (pintype "passive+no_connect"))
    )
    (net (code "74") (name "unconnected-(Transf1-Pad8)") (class "Default")
      (node (ref "Transf1") (pin "8") (pintype "passive+no_connect"))
    )
    (net (code "75") (name "unconnected-(Transf1-Pad9)") (class "Default")
      (node (ref "Transf1") (pin "9") (pintype "passive+no_connect"))
    )
    (net (code "76") (name "unconnected-(Transf1-Prime2--Pad5)") (class "Default")
      (node (ref "Transf1") (pin "5") (pinfunction "Prime2-_5") (pintype "passive+no_connect"))
    )
    (net (code "77") (name "unconnected-(U3-CLK-Pad38)") (class "Default")
      (node (ref "U3") (pin "38") (pinfunction "CLK_38") (pintype "input"))
    )
    (net (code "78") (name "unconnected-(U3-CMD-Pad18)") (class "Default")
      (node (ref "U3") (pin "18") (pinfunction "CMD_18") (pintype "bidirectional"))
    )
    (net (code "79") (name "unconnected-(U3-EN-Pad2)") (class "Default")
      (node (ref "U3") (pin "2") (pinfunction "EN_2") (pintype "input"))
    )
    (net (code "80") (name "unconnected-(U3-IO2-Pad34)") (class "Default")
      (node (ref "U3") (pin "34") (pinfunction "IO2_34") (pintype "bidirectional"))
    )
    (net (code "81") (name "unconnected-(U3-IO5-Pad29)") (class "Default")
      (node (ref "U3") (pin "29") (pinfunction "IO5_29") (pintype "bidirectional"))
    )
    (net (code "82") (name "unconnected-(U3-IO12-Pad13)") (class "Default")
      (node (ref "U3") (pin "13") (pinfunction "IO12_13") (pintype "bidirectional"))
    )
    (net (code "83") (name "unconnected-(U3-IO13-Pad15)") (class "Default")
      (node (ref "U3") (pin "15") (pinfunction "IO13_15") (pintype "bidirectional"))
    )
    (net (code "84") (name "unconnected-(U3-IO14-Pad12)") (class "Default")
      (node (ref "U3") (pin "12") (pinfunction "IO14_12") (pintype "bidirectional"))
    )
    (net (code "85") (name "unconnected-(U3-IO18-Pad28)") (class "Default")
      (node (ref "U3") (pin "28") (pinfunction "IO18_28") (pintype "bidirectional"))
    )
    (net (code "86") (name "unconnected-(U3-IO19-Pad27)") (class "Default")
      (node (ref "U3") (pin "27") (pinfunction "IO19_27") (pintype "bidirectional"))
    )
    (net (code "87") (name "unconnected-(U3-IO23-Pad21)") (class "Default")
      (node (ref "U3") (pin "21") (pinfunction "IO23_21") (pintype "bidirectional"))
    )
    (net (code "88") (name "unconnected-(U3-IO25-Pad9)") (class "Default")
      (node (ref "U3") (pin "9") (pinfunction "IO25_9") (pintype "bidirectional"))
    )
    (net (code "89") (name "unconnected-(U3-IO26-Pad10)") (class "Default")
      (node (ref "U3") (pin "10") (pinfunction "IO26_10") (pintype "bidirectional"))
    )
    (net (code "90") (name "unconnected-(U3-IO27-Pad11)") (class "Default")
      (node (ref "U3") (pin "11") (pinfunction "IO27_11") (pintype "bidirectional"))
    )
    (net (code "91") (name "unconnected-(U3-IO34-Pad5)") (class "Default")
      (node (ref "U3") (pin "5") (pinfunction "IO34_5") (pintype "bidirectional"))
    )
    (net (code "92") (name "unconnected-(U3-IO35-Pad6)") (class "Default")
      (node (ref "U3") (pin "6") (pinfunction "IO35_6") (pintype "bidirectional"))
    )
    (net (code "93") (name "unconnected-(U3-RXD0-Pad24)") (class "Default")
      (node (ref "U3") (pin "24") (pinfunction "RXD0_24") (pintype "input"))
    )
    (net (code "94") (name "unconnected-(U3-SD0-Pad37)") (class "Default")
      (node (ref "U3") (pin "37") (pinfunction "SD0_37") (pintype "bidirectional"))
    )
    (net (code "95") (name "unconnected-(U3-SD1-Pad36)") (class "Default")
      (node (ref "U3") (pin "36") (pinfunction "SD1_36") (pintype "bidirectional"))
    )
    (net (code "96") (name "unconnected-(U3-SD2-Pad16)") (class "Default")
      (node (ref "U3") (pin "16") (pinfunction "SD2_16") (pintype "bidirectional"))
    )
    (net (code "97") (name "unconnected-(U3-SD3-Pad17)") (class "Default")
      (node (ref "U3") (pin "17") (pinfunction "SD3_17") (pintype "bidirectional"))
    )
    (net (code "98") (name "unconnected-(U3-SENSOR_VN-Pad4)") (class "Default")
      (node (ref "U3") (pin "4") (pinfunction "SENSOR_VN_4") (pintype "input"))
    )
    (net (code "99") (name "unconnected-(U3-SENSOR_VP-Pad3)") (class "Default")
      (node (ref "U3") (pin "3") (pinfunction "SENSOR_VP_3") (pintype "input"))
    )
    (net (code "100") (name "unconnected-(U3-TXD0-Pad23)") (class "Default")
      (node (ref "U3") (pin "23") (pinfunction "TXD0_23") (pintype "output"))
    )
  )
)
